# LPDDR4_SDRAM-1.net
KiCad netlist of a schematic drawn in Altium Designer
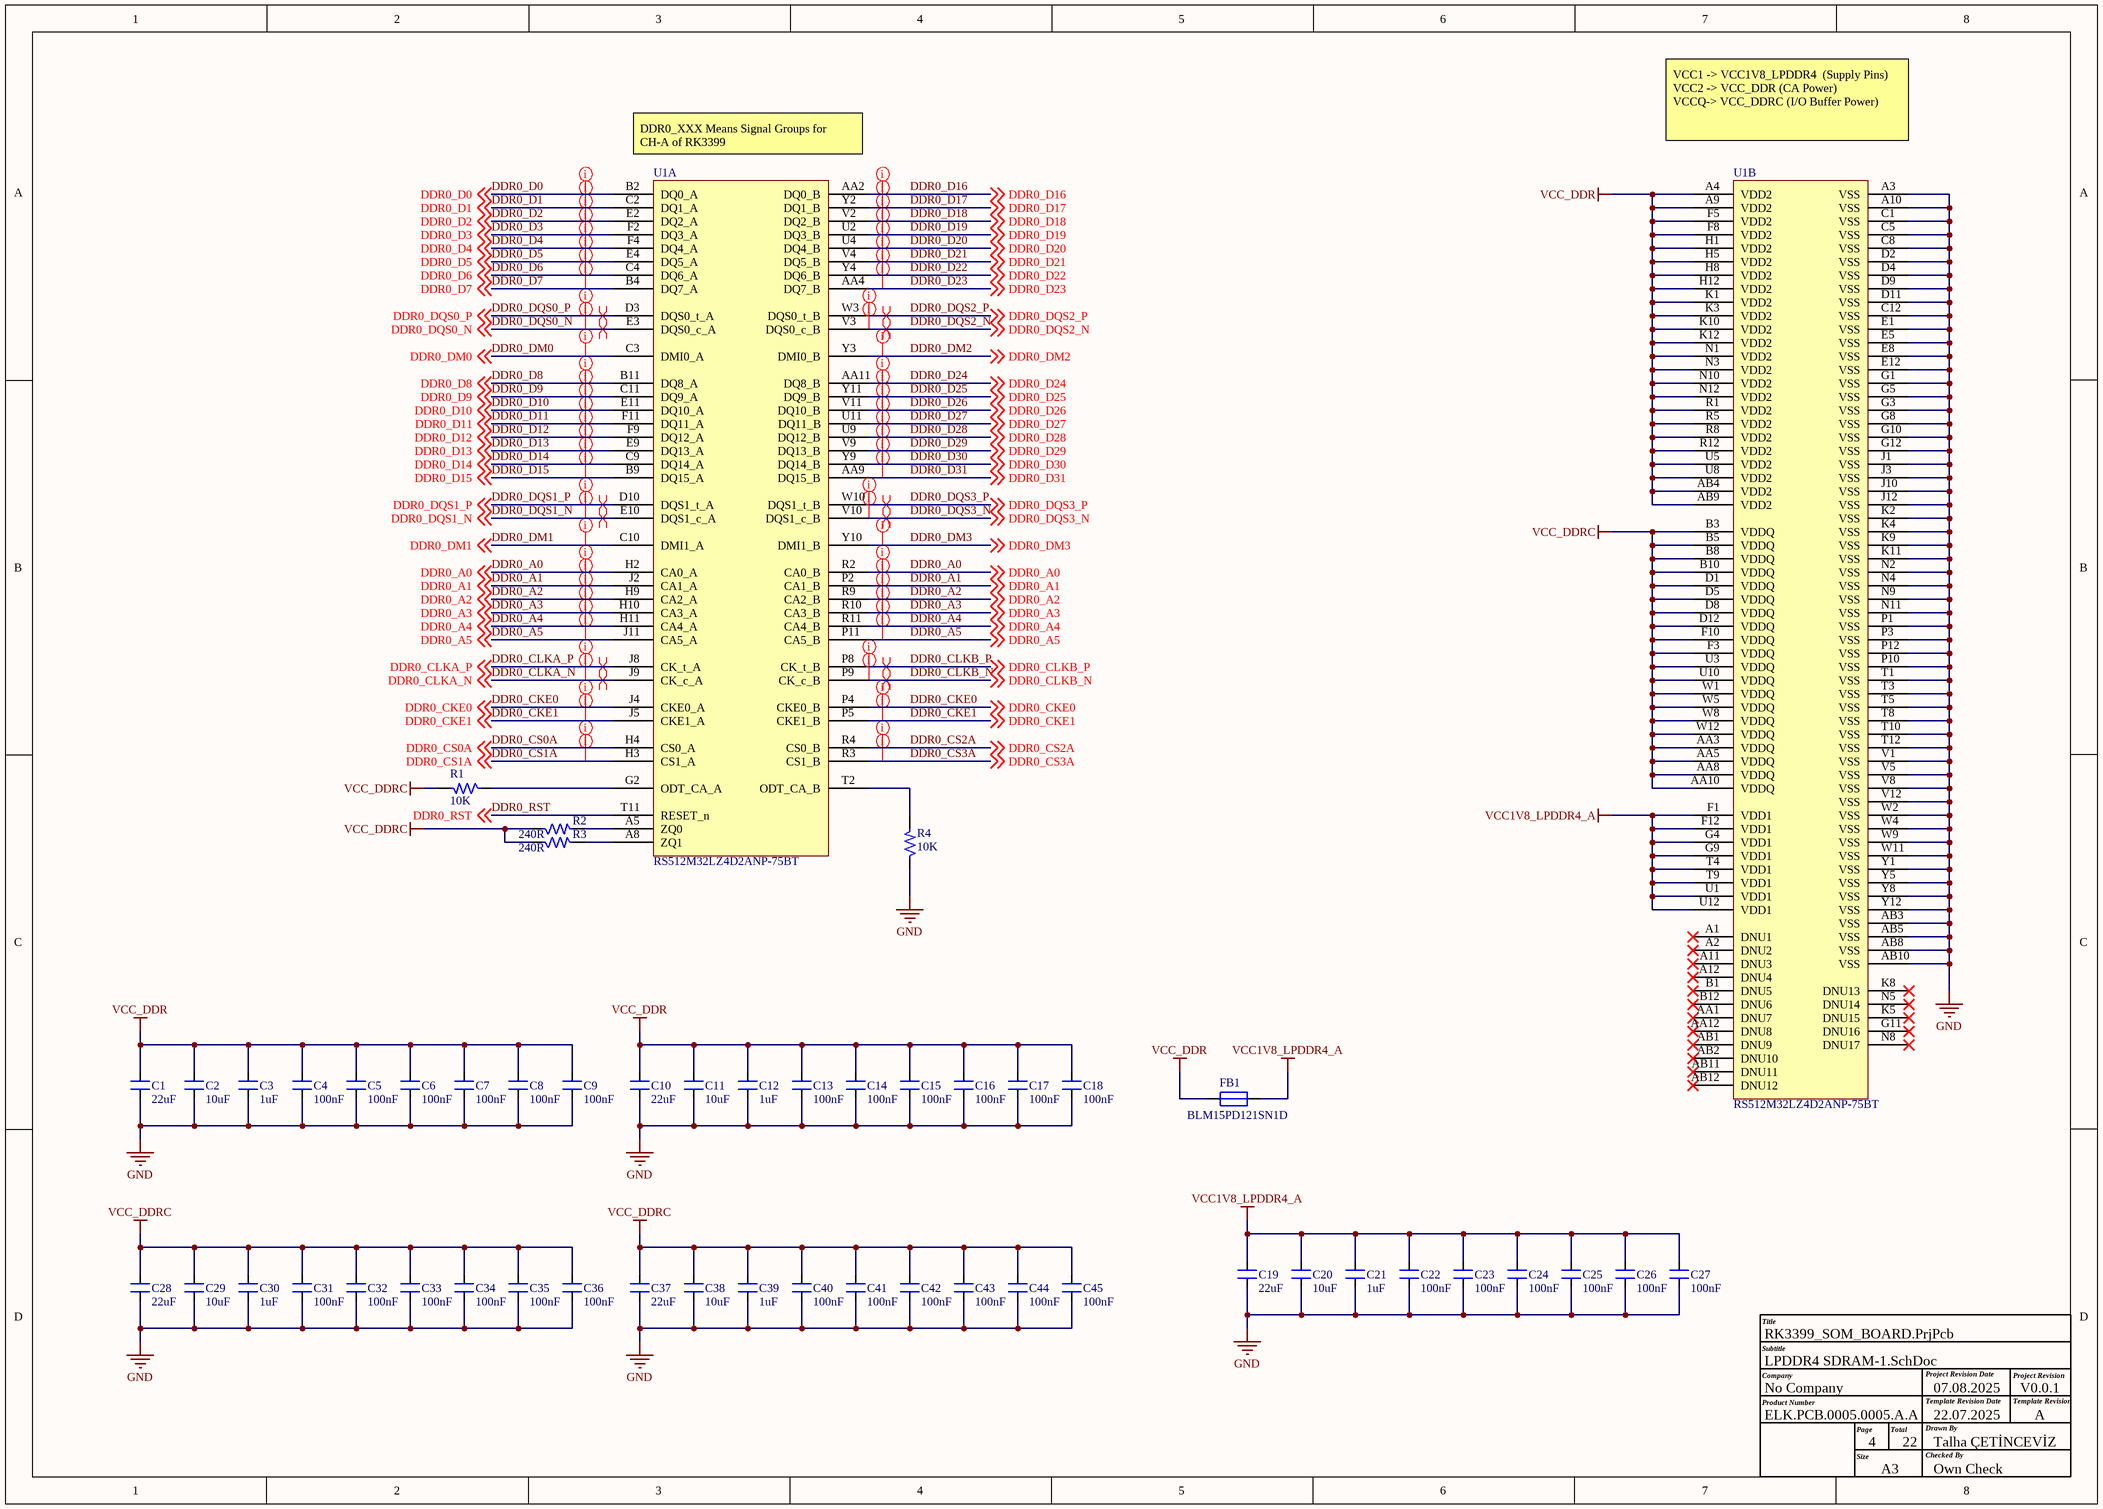
[diagram p0: LPDDR4 SDRAM-1.SchDoc]

(export (version "E")
  (design (tool "Eeschema 10.0.6"))
  (components
    (comp (ref "C1")
      (value "22uF")
      (footprint "CAP_0402")
      (description "22µF ±20% 6.3V Ceramic Capacitor X5R 0402 (1005 Metric)")
      (fields
        (field (name "MANUFACTURER") "Murata Electronics")
        (field (name "MANUFACTURER PART NUMBER") "CL05A226MQ5N6J8")
      )
      (libsource (lib "EsteemPCB_SOM_Course_intlib") (part "CAP_22uF-6.3V-20%-0402"))
    )
    (comp (ref "C2")
      (value "10uF")
      (footprint "CAP_0402")
      (description "10µF ±20% 10V Ceramic Capacitor X5R 0402 (1005 Metric)")
      (fields
        (field (name "MANUFACTURER PART NUMBER") "CL05A106MP5NUNC")
        (field (name "MANUFACTURER") "Samsung Electro-Mechanics")
      )
      (libsource (lib "EsteemPCB_SOM_Course_intlib") (part "CAP_10uF-10V-20%-0402"))
    )
    (comp (ref "C3")
      (value "1uF")
      (footprint "CAP_0201")
      (description "1µF ±20% 16V Ceramic Capacitor X5R 0201 (0603 Metric)")
      (fields
        (field (name "MANUFACTURER") "Samsung Electro-Mechanics")
        (field (name "MANUFACTURER PART NUMBER") "CL03A105MO3NRNH")
      )
      (libsource (lib "EsteemPCB_SOM_Course_intlib") (part "CAP_1uF-16V-10%-0201"))
    )
    (comp (ref "C4")
      (value "100nF")
      (footprint "CAP_0201")
      (description "0.1µF ±10% 25V Ceramic Capacitor X5R 0201 (0603 Metric)")
      (fields
        (field (name "MANUFACTURER") "TDK Corporation")
        (field (name "MANUFACTURER PART NUMBER") "C0603X5R1E104K030BB")
      )
      (libsource (lib "EsteemPCB_SOM_Course_intlib") (part "CAP_100nF-25V-10%-0201"))
    )
    (comp (ref "C5")
      (value "100nF")
      (footprint "CAP_0201")
      (description "0.1µF ±10% 25V Ceramic Capacitor X5R 0201 (0603 Metric)")
      (fields
        (field (name "MANUFACTURER") "TDK Corporation")
        (field (name "MANUFACTURER PART NUMBER") "C0603X5R1E104K030BB")
      )
      (libsource (lib "EsteemPCB_SOM_Course_intlib") (part "CAP_100nF-25V-10%-0201"))
    )
    (comp (ref "C6")
      (value "100nF")
      (footprint "CAP_0201")
      (description "0.1µF ±10% 25V Ceramic Capacitor X5R 0201 (0603 Metric)")
      (fields
        (field (name "MANUFACTURER") "TDK Corporation")
        (field (name "MANUFACTURER PART NUMBER") "C0603X5R1E104K030BB")
      )
      (libsource (lib "EsteemPCB_SOM_Course_intlib") (part "CAP_100nF-25V-10%-0201"))
    )
    (comp (ref "C7")
      (value "100nF")
      (footprint "CAP_0201")
      (description "0.1µF ±10% 25V Ceramic Capacitor X5R 0201 (0603 Metric)")
      (fields
        (field (name "MANUFACTURER") "TDK Corporation")
        (field (name "MANUFACTURER PART NUMBER") "C0603X5R1E104K030BB")
      )
      (libsource (lib "EsteemPCB_SOM_Course_intlib") (part "CAP_100nF-25V-10%-0201"))
    )
    (comp (ref "C8")
      (value "100nF")
      (footprint "CAP_0201")
      (description "0.1µF ±10% 25V Ceramic Capacitor X5R 0201 (0603 Metric)")
      (fields
        (field (name "MANUFACTURER") "TDK Corporation")
        (field (name "MANUFACTURER PART NUMBER") "C0603X5R1E104K030BB")
      )
      (libsource (lib "EsteemPCB_SOM_Course_intlib") (part "CAP_100nF-25V-10%-0201"))
    )
    (comp (ref "C9")
      (value "100nF")
      (footprint "CAP_0201")
      (description "0.1µF ±10% 25V Ceramic Capacitor X5R 0201 (0603 Metric)")
      (fields
        (field (name "MANUFACTURER") "TDK Corporation")
        (field (name "MANUFACTURER PART NUMBER") "C0603X5R1E104K030BB")
      )
      (libsource (lib "EsteemPCB_SOM_Course_intlib") (part "CAP_100nF-25V-10%-0201"))
    )
    (comp (ref "C10")
      (value "22uF")
      (footprint "CAP_0402")
      (description "22µF ±20% 6.3V Ceramic Capacitor X5R 0402 (1005 Metric)")
      (fields
        (field (name "MANUFACTURER") "Murata Electronics")
        (field (name "MANUFACTURER PART NUMBER") "CL05A226MQ5N6J8")
      )
      (libsource (lib "EsteemPCB_SOM_Course_intlib") (part "CAP_22uF-6.3V-20%-0402"))
    )
    (comp (ref "C11")
      (value "10uF")
      (footprint "CAP_0402")
      (description "10µF ±20% 10V Ceramic Capacitor X5R 0402 (1005 Metric)")
      (fields
        (field (name "MANUFACTURER PART NUMBER") "CL05A106MP5NUNC")
        (field (name "MANUFACTURER") "Samsung Electro-Mechanics")
      )
      (libsource (lib "EsteemPCB_SOM_Course_intlib") (part "CAP_10uF-10V-20%-0402"))
    )
    (comp (ref "C12")
      (value "1uF")
      (footprint "CAP_0201")
      (description "1µF ±20% 16V Ceramic Capacitor X5R 0201 (0603 Metric)")
      (fields
        (field (name "MANUFACTURER") "Samsung Electro-Mechanics")
        (field (name "MANUFACTURER PART NUMBER") "CL03A105MO3NRNH")
      )
      (libsource (lib "EsteemPCB_SOM_Course_intlib") (part "CAP_1uF-16V-10%-0201"))
    )
    (comp (ref "C13")
      (value "100nF")
      (footprint "CAP_0201")
      (description "0.1µF ±10% 25V Ceramic Capacitor X5R 0201 (0603 Metric)")
      (fields
        (field (name "MANUFACTURER") "TDK Corporation")
        (field (name "MANUFACTURER PART NUMBER") "C0603X5R1E104K030BB")
      )
      (libsource (lib "EsteemPCB_SOM_Course_intlib") (part "CAP_100nF-25V-10%-0201"))
    )
    (comp (ref "C14")
      (value "100nF")
      (footprint "CAP_0201")
      (description "0.1µF ±10% 25V Ceramic Capacitor X5R 0201 (0603 Metric)")
      (fields
        (field (name "MANUFACTURER") "TDK Corporation")
        (field (name "MANUFACTURER PART NUMBER") "C0603X5R1E104K030BB")
      )
      (libsource (lib "EsteemPCB_SOM_Course_intlib") (part "CAP_100nF-25V-10%-0201"))
    )
    (comp (ref "C15")
      (value "100nF")
      (footprint "CAP_0201")
      (description "0.1µF ±10% 25V Ceramic Capacitor X5R 0201 (0603 Metric)")
      (fields
        (field (name "MANUFACTURER") "TDK Corporation")
        (field (name "MANUFACTURER PART NUMBER") "C0603X5R1E104K030BB")
      )
      (libsource (lib "EsteemPCB_SOM_Course_intlib") (part "CAP_100nF-25V-10%-0201"))
    )
    (comp (ref "C16")
      (value "100nF")
      (footprint "CAP_0201")
      (description "0.1µF ±10% 25V Ceramic Capacitor X5R 0201 (0603 Metric)")
      (fields
        (field (name "MANUFACTURER") "TDK Corporation")
        (field (name "MANUFACTURER PART NUMBER") "C0603X5R1E104K030BB")
      )
      (libsource (lib "EsteemPCB_SOM_Course_intlib") (part "CAP_100nF-25V-10%-0201"))
    )
    (comp (ref "C17")
      (value "100nF")
      (footprint "CAP_0201")
      (description "0.1µF ±10% 25V Ceramic Capacitor X5R 0201 (0603 Metric)")
      (fields
        (field (name "MANUFACTURER") "TDK Corporation")
        (field (name "MANUFACTURER PART NUMBER") "C0603X5R1E104K030BB")
      )
      (libsource (lib "EsteemPCB_SOM_Course_intlib") (part "CAP_100nF-25V-10%-0201"))
    )
    (comp (ref "C18")
      (value "100nF")
      (footprint "CAP_0201")
      (description "0.1µF ±10% 25V Ceramic Capacitor X5R 0201 (0603 Metric)")
      (fields
        (field (name "MANUFACTURER") "TDK Corporation")
        (field (name "MANUFACTURER PART NUMBER") "C0603X5R1E104K030BB")
      )
      (libsource (lib "EsteemPCB_SOM_Course_intlib") (part "CAP_100nF-25V-10%-0201"))
    )
    (comp (ref "C19")
      (value "22uF")
      (footprint "CAP_0402")
      (description "22µF ±20% 6.3V Ceramic Capacitor X5R 0402 (1005 Metric)")
      (fields
        (field (name "MANUFACTURER") "Murata Electronics")
        (field (name "MANUFACTURER PART NUMBER") "CL05A226MQ5N6J8")
      )
      (libsource (lib "EsteemPCB_SOM_Course_intlib") (part "CAP_22uF-6.3V-20%-0402"))
    )
    (comp (ref "C20")
      (value "10uF")
      (footprint "CAP_0402")
      (description "10µF ±20% 10V Ceramic Capacitor X5R 0402 (1005 Metric)")
      (fields
        (field (name "MANUFACTURER PART NUMBER") "CL05A106MP5NUNC")
        (field (name "MANUFACTURER") "Samsung Electro-Mechanics")
      )
      (libsource (lib "EsteemPCB_SOM_Course_intlib") (part "CAP_10uF-10V-20%-0402"))
    )
    (comp (ref "C21")
      (value "1uF")
      (footprint "CAP_0201")
      (description "1µF ±20% 16V Ceramic Capacitor X5R 0201 (0603 Metric)")
      (fields
        (field (name "MANUFACTURER") "Samsung Electro-Mechanics")
        (field (name "MANUFACTURER PART NUMBER") "CL03A105MO3NRNH")
      )
      (libsource (lib "EsteemPCB_SOM_Course_intlib") (part "CAP_1uF-16V-10%-0201"))
    )
    (comp (ref "C22")
      (value "100nF")
      (footprint "CAP_0201")
      (description "0.1µF ±10% 25V Ceramic Capacitor X5R 0201 (0603 Metric)")
      (fields
        (field (name "MANUFACTURER") "TDK Corporation")
        (field (name "MANUFACTURER PART NUMBER") "C0603X5R1E104K030BB")
      )
      (libsource (lib "EsteemPCB_SOM_Course_intlib") (part "CAP_100nF-25V-10%-0201"))
    )
    (comp (ref "C23")
      (value "100nF")
      (footprint "CAP_0201")
      (description "0.1µF ±10% 25V Ceramic Capacitor X5R 0201 (0603 Metric)")
      (fields
        (field (name "MANUFACTURER") "TDK Corporation")
        (field (name "MANUFACTURER PART NUMBER") "C0603X5R1E104K030BB")
      )
      (libsource (lib "EsteemPCB_SOM_Course_intlib") (part "CAP_100nF-25V-10%-0201"))
    )
    (comp (ref "C24")
      (value "100nF")
      (footprint "CAP_0201")
      (description "0.1µF ±10% 25V Ceramic Capacitor X5R 0201 (0603 Metric)")
      (fields
        (field (name "MANUFACTURER") "TDK Corporation")
        (field (name "MANUFACTURER PART NUMBER") "C0603X5R1E104K030BB")
      )
      (libsource (lib "EsteemPCB_SOM_Course_intlib") (part "CAP_100nF-25V-10%-0201"))
    )
    (comp (ref "C25")
      (value "100nF")
      (footprint "CAP_0201")
      (description "0.1µF ±10% 25V Ceramic Capacitor X5R 0201 (0603 Metric)")
      (fields
        (field (name "MANUFACTURER") "TDK Corporation")
        (field (name "MANUFACTURER PART NUMBER") "C0603X5R1E104K030BB")
      )
      (libsource (lib "EsteemPCB_SOM_Course_intlib") (part "CAP_100nF-25V-10%-0201"))
    )
    (comp (ref "C26")
      (value "100nF")
      (footprint "CAP_0201")
      (description "0.1µF ±10% 25V Ceramic Capacitor X5R 0201 (0603 Metric)")
      (fields
        (field (name "MANUFACTURER") "TDK Corporation")
        (field (name "MANUFACTURER PART NUMBER") "C0603X5R1E104K030BB")
      )
      (libsource (lib "EsteemPCB_SOM_Course_intlib") (part "CAP_100nF-25V-10%-0201"))
    )
    (comp (ref "C27")
      (value "100nF")
      (footprint "CAP_0201")
      (description "0.1µF ±10% 25V Ceramic Capacitor X5R 0201 (0603 Metric)")
      (fields
        (field (name "MANUFACTURER") "TDK Corporation")
        (field (name "MANUFACTURER PART NUMBER") "C0603X5R1E104K030BB")
      )
      (libsource (lib "EsteemPCB_SOM_Course_intlib") (part "CAP_100nF-25V-10%-0201"))
    )
    (comp (ref "C28")
      (value "22uF")
      (footprint "CAP_0402")
      (description "22µF ±20% 6.3V Ceramic Capacitor X5R 0402 (1005 Metric)")
      (fields
        (field (name "MANUFACTURER") "Murata Electronics")
        (field (name "MANUFACTURER PART NUMBER") "CL05A226MQ5N6J8")
      )
      (libsource (lib "EsteemPCB_SOM_Course_intlib") (part "CAP_22uF-6.3V-20%-0402"))
    )
    (comp (ref "C29")
      (value "10uF")
      (footprint "CAP_0402")
      (description "10µF ±20% 10V Ceramic Capacitor X5R 0402 (1005 Metric)")
      (fields
        (field (name "MANUFACTURER PART NUMBER") "CL05A106MP5NUNC")
        (field (name "MANUFACTURER") "Samsung Electro-Mechanics")
      )
      (libsource (lib "EsteemPCB_SOM_Course_intlib") (part "CAP_10uF-10V-20%-0402"))
    )
    (comp (ref "C30")
      (value "1uF")
      (footprint "CAP_0201")
      (description "1µF ±20% 16V Ceramic Capacitor X5R 0201 (0603 Metric)")
      (fields
        (field (name "MANUFACTURER") "Samsung Electro-Mechanics")
        (field (name "MANUFACTURER PART NUMBER") "CL03A105MO3NRNH")
      )
      (libsource (lib "EsteemPCB_SOM_Course_intlib") (part "CAP_1uF-16V-10%-0201"))
    )
    (comp (ref "C31")
      (value "100nF")
      (footprint "CAP_0201")
      (description "0.1µF ±10% 25V Ceramic Capacitor X5R 0201 (0603 Metric)")
      (fields
        (field (name "MANUFACTURER") "TDK Corporation")
        (field (name "MANUFACTURER PART NUMBER") "C0603X5R1E104K030BB")
      )
      (libsource (lib "EsteemPCB_SOM_Course_intlib") (part "CAP_100nF-25V-10%-0201"))
    )
    (comp (ref "C32")
      (value "100nF")
      (footprint "CAP_0201")
      (description "0.1µF ±10% 25V Ceramic Capacitor X5R 0201 (0603 Metric)")
      (fields
        (field (name "MANUFACTURER") "TDK Corporation")
        (field (name "MANUFACTURER PART NUMBER") "C0603X5R1E104K030BB")
      )
      (libsource (lib "EsteemPCB_SOM_Course_intlib") (part "CAP_100nF-25V-10%-0201"))
    )
    (comp (ref "C33")
      (value "100nF")
      (footprint "CAP_0201")
      (description "0.1µF ±10% 25V Ceramic Capacitor X5R 0201 (0603 Metric)")
      (fields
        (field (name "MANUFACTURER") "TDK Corporation")
        (field (name "MANUFACTURER PART NUMBER") "C0603X5R1E104K030BB")
      )
      (libsource (lib "EsteemPCB_SOM_Course_intlib") (part "CAP_100nF-25V-10%-0201"))
    )
    (comp (ref "C34")
      (value "100nF")
      (footprint "CAP_0201")
      (description "0.1µF ±10% 25V Ceramic Capacitor X5R 0201 (0603 Metric)")
      (fields
        (field (name "MANUFACTURER") "TDK Corporation")
        (field (name "MANUFACTURER PART NUMBER") "C0603X5R1E104K030BB")
      )
      (libsource (lib "EsteemPCB_SOM_Course_intlib") (part "CAP_100nF-25V-10%-0201"))
    )
    (comp (ref "C35")
      (value "100nF")
      (footprint "CAP_0201")
      (description "0.1µF ±10% 25V Ceramic Capacitor X5R 0201 (0603 Metric)")
      (fields
        (field (name "MANUFACTURER") "TDK Corporation")
        (field (name "MANUFACTURER PART NUMBER") "C0603X5R1E104K030BB")
      )
      (libsource (lib "EsteemPCB_SOM_Course_intlib") (part "CAP_100nF-25V-10%-0201"))
    )
    (comp (ref "C36")
      (value "100nF")
      (footprint "CAP_0201")
      (description "0.1µF ±10% 25V Ceramic Capacitor X5R 0201 (0603 Metric)")
      (fields
        (field (name "MANUFACTURER") "TDK Corporation")
        (field (name "MANUFACTURER PART NUMBER") "C0603X5R1E104K030BB")
      )
      (libsource (lib "EsteemPCB_SOM_Course_intlib") (part "CAP_100nF-25V-10%-0201"))
    )
    (comp (ref "C37")
      (value "22uF")
      (footprint "CAP_0402")
      (description "22µF ±20% 6.3V Ceramic Capacitor X5R 0402 (1005 Metric)")
      (fields
        (field (name "MANUFACTURER") "Murata Electronics")
        (field (name "MANUFACTURER PART NUMBER") "CL05A226MQ5N6J8")
      )
      (libsource (lib "EsteemPCB_SOM_Course_intlib") (part "CAP_22uF-6.3V-20%-0402"))
    )
    (comp (ref "C38")
      (value "10uF")
      (footprint "CAP_0402")
      (description "10µF ±20% 10V Ceramic Capacitor X5R 0402 (1005 Metric)")
      (fields
        (field (name "MANUFACTURER PART NUMBER") "CL05A106MP5NUNC")
        (field (name "MANUFACTURER") "Samsung Electro-Mechanics")
      )
      (libsource (lib "EsteemPCB_SOM_Course_intlib") (part "CAP_10uF-10V-20%-0402"))
    )
    (comp (ref "C39")
      (value "1uF")
      (footprint "CAP_0201")
      (description "1µF ±20% 16V Ceramic Capacitor X5R 0201 (0603 Metric)")
      (fields
        (field (name "MANUFACTURER") "Samsung Electro-Mechanics")
        (field (name "MANUFACTURER PART NUMBER") "CL03A105MO3NRNH")
      )
      (libsource (lib "EsteemPCB_SOM_Course_intlib") (part "CAP_1uF-16V-10%-0201"))
    )
    (comp (ref "C40")
      (value "100nF")
      (footprint "CAP_0201")
      (description "0.1µF ±10% 25V Ceramic Capacitor X5R 0201 (0603 Metric)")
      (fields
        (field (name "MANUFACTURER") "TDK Corporation")
        (field (name "MANUFACTURER PART NUMBER") "C0603X5R1E104K030BB")
      )
      (libsource (lib "EsteemPCB_SOM_Course_intlib") (part "CAP_100nF-25V-10%-0201"))
    )
    (comp (ref "C41")
      (value "100nF")
      (footprint "CAP_0201")
      (description "0.1µF ±10% 25V Ceramic Capacitor X5R 0201 (0603 Metric)")
      (fields
        (field (name "MANUFACTURER") "TDK Corporation")
        (field (name "MANUFACTURER PART NUMBER") "C0603X5R1E104K030BB")
      )
      (libsource (lib "EsteemPCB_SOM_Course_intlib") (part "CAP_100nF-25V-10%-0201"))
    )
    (comp (ref "C42")
      (value "100nF")
      (footprint "CAP_0201")
      (description "0.1µF ±10% 25V Ceramic Capacitor X5R 0201 (0603 Metric)")
      (fields
        (field (name "MANUFACTURER") "TDK Corporation")
        (field (name "MANUFACTURER PART NUMBER") "C0603X5R1E104K030BB")
      )
      (libsource (lib "EsteemPCB_SOM_Course_intlib") (part "CAP_100nF-25V-10%-0201"))
    )
    (comp (ref "C43")
      (value "100nF")
      (footprint "CAP_0201")
      (description "0.1µF ±10% 25V Ceramic Capacitor X5R 0201 (0603 Metric)")
      (fields
        (field (name "MANUFACTURER") "TDK Corporation")
        (field (name "MANUFACTURER PART NUMBER") "C0603X5R1E104K030BB")
      )
      (libsource (lib "EsteemPCB_SOM_Course_intlib") (part "CAP_100nF-25V-10%-0201"))
    )
    (comp (ref "C44")
      (value "100nF")
      (footprint "CAP_0201")
      (description "0.1µF ±10% 25V Ceramic Capacitor X5R 0201 (0603 Metric)")
      (fields
        (field (name "MANUFACTURER") "TDK Corporation")
        (field (name "MANUFACTURER PART NUMBER") "C0603X5R1E104K030BB")
      )
      (libsource (lib "EsteemPCB_SOM_Course_intlib") (part "CAP_100nF-25V-10%-0201"))
    )
    (comp (ref "C45")
      (value "100nF")
      (footprint "CAP_0201")
      (description "0.1µF ±10% 25V Ceramic Capacitor X5R 0201 (0603 Metric)")
      (fields
        (field (name "MANUFACTURER") "TDK Corporation")
        (field (name "MANUFACTURER PART NUMBER") "C0603X5R1E104K030BB")
      )
      (libsource (lib "EsteemPCB_SOM_Course_intlib") (part "CAP_100nF-25V-10%-0201"))
    )
    (comp (ref "FB1")
      (value "BLM15PD121SN1D")
      (footprint "RES_0402")
      (description "120 Ohms @ 100MHz 1 Power Line Ferrite Bead 0402 (1005 Metric) 1.3A 90mOhm")
      (fields (field (name "MANUFACTURER") "Murata Electronics"))
      (libsource (lib "EsteemPCB_SOM_Course_intlib") (part "FB_120R-1.3A-100Mhz-0402"))
    )
    (comp (ref "R1")
      (value "10K")
      (footprint "RES_0201")
      (description "10 kOhms ±1% 0.05W, 1/20W Chip Resistor 0201 (0603 Metric) Thick Film")
      (fields
        (field (name "MANUFACTURER") "Stackpole Electronics Inc")
        (field (name "MANUFACTURER PART NUMBER") "RMCF0201FT10K0")
      )
      (libsource (lib "EsteemPCB_SOM_Course_intlib") (part "RES_10K-0.05W-1%-0201"))
    )
    (comp (ref "R2")
      (value "240R")
      (footprint "RES_0201")
      (description "240 Ohms ±1% 0.05W, 1/20W Chip Resistor 0201 (0603 Metric) Thick Film")
      (fields
        (field (name "MANUFACTURER") "Yageo")
        (field (name "MANUFACTURER PART NUMBER") "RC0201FR-07240RL")
      )
      (libsource (lib "EsteemPCB_SOM_Course_intlib") (part "RES_240R-0.05W-1%-0201"))
    )
    (comp (ref "R3")
      (value "240R")
      (footprint "RES_0201")
      (description "240 Ohms ±1% 0.05W, 1/20W Chip Resistor 0201 (0603 Metric) Thick Film")
      (fields
        (field (name "MANUFACTURER") "Yageo")
        (field (name "MANUFACTURER PART NUMBER") "RC0201FR-07240RL")
      )
      (libsource (lib "EsteemPCB_SOM_Course_intlib") (part "RES_240R-0.05W-1%-0201"))
    )
    (comp (ref "R4")
      (value "10K")
      (footprint "RES_0201")
      (description "10 kOhms ±1% 0.05W, 1/20W Chip Resistor 0201 (0603 Metric) Thick Film")
      (fields
        (field (name "MANUFACTURER") "Stackpole Electronics Inc")
        (field (name "MANUFACTURER PART NUMBER") "RMCF0201FT10K0")
      )
      (libsource (lib "EsteemPCB_SOM_Course_intlib") (part "RES_10K-0.05W-1%-0201"))
    )
    (comp (ref "U1")
      (value "RS512M32LZ4D2ANP-75BT")
      (footprint "FBGA200_SMD")
      (fields (field (name "MANUFACTURER") "RAYSON"))
      (libsource (lib "EsteemPCB_SOM_Course_intlib") (part "IC_RS512M32LZ4D2ANP-75BT"))
    )
  )
  (nets
    (net (code "1") (name "DDR0_A0") (class "Default")
      (node (ref "U1") (pin "H2") (pinfunction "CA0_A_H2") (pintype "passive"))
      (node (ref "U1") (pin "R2") (pinfunction "CA0_B_R2") (pintype "passive"))
    )
    (net (code "2") (name "DDR0_A1") (class "Default")
      (node (ref "U1") (pin "J2") (pinfunction "CA1_A_J2") (pintype "passive"))
      (node (ref "U1") (pin "P2") (pinfunction "CA1_B_P2") (pintype "passive"))
    )
    (net (code "3") (name "DDR0_A2") (class "Default")
      (node (ref "U1") (pin "H9") (pinfunction "CA2_A_H9") (pintype "passive"))
      (node (ref "U1") (pin "R9") (pinfunction "CA2_B_R9") (pintype "passive"))
    )
    (net (code "4") (name "DDR0_A3") (class "Default")
      (node (ref "U1") (pin "H10") (pinfunction "CA3_A_H10") (pintype "passive"))
      (node (ref "U1") (pin "R10") (pinfunction "CA3_B_R10") (pintype "passive"))
    )
    (net (code "5") (name "DDR0_A4") (class "Default")
      (node (ref "U1") (pin "H11") (pinfunction "CA4_A_H11") (pintype "passive"))
      (node (ref "U1") (pin "R11") (pinfunction "CA4_B_R11") (pintype "passive"))
    )
    (net (code "6") (name "DDR0_A5") (class "Default")
      (node (ref "U1") (pin "J11") (pinfunction "CA5_A_J11") (pintype "passive"))
      (node (ref "U1") (pin "P11") (pinfunction "CA5_B_P11") (pintype "passive"))
    )
    (net (code "7") (name "DDR0_CKE0") (class "Default")
      (node (ref "U1") (pin "J4") (pinfunction "CKE0_A_J4") (pintype "passive"))
      (node (ref "U1") (pin "P4") (pinfunction "CKE0_B_P4") (pintype "passive"))
    )
    (net (code "8") (name "DDR0_CKE1") (class "Default")
      (node (ref "U1") (pin "J5") (pinfunction "CKE1_A_J5") (pintype "passive"))
      (node (ref "U1") (pin "P5") (pinfunction "CKE1_B_P5") (pintype "passive"))
    )
    (net (code "9") (name "DDR0_CLKA_N") (class "Default")
      (node (ref "U1") (pin "J9") (pinfunction "CK_c_A_J9") (pintype "passive"))
    )
    (net (code "10") (name "DDR0_CLKA_P") (class "Default")
      (node (ref "U1") (pin "J8") (pinfunction "CK_t_A_J8") (pintype "passive"))
    )
    (net (code "11") (name "DDR0_CLKB_N") (class "Default")
      (node (ref "U1") (pin "P9") (pinfunction "CK_c_B_P9") (pintype "passive"))
    )
    (net (code "12") (name "DDR0_CLKB_P") (class "Default")
      (node (ref "U1") (pin "P8") (pinfunction "CK_t_B_P8") (pintype "passive"))
    )
    (net (code "13") (name "DDR0_CS0A") (class "Default")
      (node (ref "U1") (pin "H4") (pinfunction "CS0_A_H4") (pintype "passive"))
    )
    (net (code "14") (name "DDR0_CS1A") (class "Default")
      (node (ref "U1") (pin "H3") (pinfunction "CS1_A_H3") (pintype "passive"))
    )
    (net (code "15") (name "DDR0_CS2A") (class "Default")
      (node (ref "U1") (pin "R4") (pinfunction "CS0_B_R4") (pintype "passive"))
    )
    (net (code "16") (name "DDR0_CS3A") (class "Default")
      (node (ref "U1") (pin "R3") (pinfunction "CS1_B_R3") (pintype "passive"))
    )
    (net (code "17") (name "DDR0_D0") (class "Default")
      (node (ref "U1") (pin "B2") (pinfunction "DQ0_A_B2") (pintype "passive"))
    )
    (net (code "18") (name "DDR0_D1") (class "Default")
      (node (ref "U1") (pin "C2") (pinfunction "DQ1_A_C2") (pintype "passive"))
    )
    (net (code "19") (name "DDR0_D2") (class "Default")
      (node (ref "U1") (pin "E2") (pinfunction "DQ2_A_E2") (pintype "passive"))
    )
    (net (code "20") (name "DDR0_D3") (class "Default")
      (node (ref "U1") (pin "F2") (pinfunction "DQ3_A_F2") (pintype "passive"))
    )
    (net (code "21") (name "DDR0_D4") (class "Default")
      (node (ref "U1") (pin "F4") (pinfunction "DQ4_A_F4") (pintype "passive"))
    )
    (net (code "22") (name "DDR0_D5") (class "Default")
      (node (ref "U1") (pin "E4") (pinfunction "DQ5_A_E4") (pintype "passive"))
    )
    (net (code "23") (name "DDR0_D6") (class "Default")
      (node (ref "U1") (pin "C4") (pinfunction "DQ6_A_C4") (pintype "passive"))
    )
    (net (code "24") (name "DDR0_D7") (class "Default")
      (node (ref "U1") (pin "B4") (pinfunction "DQ7_A_B4") (pintype "passive"))
    )
    (net (code "25") (name "DDR0_D8") (class "Default")
      (node (ref "U1") (pin "B11") (pinfunction "DQ8_A_B11") (pintype "passive"))
    )
    (net (code "26") (name "DDR0_D9") (class "Default")
      (node (ref "U1") (pin "C11") (pinfunction "DQ9_A_C11") (pintype "passive"))
    )
    (net (code "27") (name "DDR0_D10") (class "Default")
      (node (ref "U1") (pin "E11") (pinfunction "DQ10_A_E11") (pintype "passive"))
    )
    (net (code "28") (name "DDR0_D11") (class "Default")
      (node (ref "U1") (pin "F11") (pinfunction "DQ11_A_F11") (pintype "passive"))
    )
    (net (code "29") (name "DDR0_D12") (class "Default")
      (node (ref "U1") (pin "F9") (pinfunction "DQ12_A_F9") (pintype "passive"))
    )
    (net (code "30") (name "DDR0_D13") (class "Default")
      (node (ref "U1") (pin "E9") (pinfunction "DQ13_A_E9") (pintype "passive"))
    )
    (net (code "31") (name "DDR0_D14") (class "Default")
      (node (ref "U1") (pin "C9") (pinfunction "DQ14_A_C9") (pintype "passive"))
    )
    (net (code "32") (name "DDR0_D15") (class "Default")
      (node (ref "U1") (pin "B9") (pinfunction "DQ15_A_B9") (pintype "passive"))
    )
    (net (code "33") (name "DDR0_D16") (class "Default")
      (node (ref "U1") (pin "AA2") (pinfunction "DQ0_B_AA2") (pintype "passive"))
    )
    (net (code "34") (name "DDR0_D17") (class "Default")
      (node (ref "U1") (pin "Y2") (pinfunction "DQ1_B_Y2") (pintype "passive"))
    )
    (net (code "35") (name "DDR0_D18") (class "Default")
      (node (ref "U1") (pin "V2") (pinfunction "DQ2_B_V2") (pintype "passive"))
    )
    (net (code "36") (name "DDR0_D19") (class "Default")
      (node (ref "U1") (pin "U2") (pinfunction "DQ3_B_U2") (pintype "passive"))
    )
    (net (code "37") (name "DDR0_D20") (class "Default")
      (node (ref "U1") (pin "U4") (pinfunction "DQ4_B_U4") (pintype "passive"))
    )
    (net (code "38") (name "DDR0_D21") (class "Default")
      (node (ref "U1") (pin "V4") (pinfunction "DQ5_B_V4") (pintype "passive"))
    )
    (net (code "39") (name "DDR0_D22") (class "Default")
      (node (ref "U1") (pin "Y4") (pinfunction "DQ6_B_Y4") (pintype "passive"))
    )
    (net (code "40") (name "DDR0_D23") (class "Default")
      (node (ref "U1") (pin "AA4") (pinfunction "DQ7_B_AA4") (pintype "passive"))
    )
    (net (code "41") (name "DDR0_D24") (class "Default")
      (node (ref "U1") (pin "AA11") (pinfunction "DQ8_B_AA11") (pintype "passive"))
    )
    (net (code "42") (name "DDR0_D25") (class "Default")
      (node (ref "U1") (pin "Y11") (pinfunction "DQ9_B_Y11") (pintype "passive"))
    )
    (net (code "43") (name "DDR0_D26") (class "Default")
      (node (ref "U1") (pin "V11") (pinfunction "DQ10_B_V11") (pintype "passive"))
    )
    (net (code "44") (name "DDR0_D27") (class "Default")
      (node (ref "U1") (pin "U11") (pinfunction "DQ11_B_U11") (pintype "passive"))
    )
    (net (code "45") (name "DDR0_D28") (class "Default")
      (node (ref "U1") (pin "U9") (pinfunction "DQ12_B_U9") (pintype "passive"))
    )
    (net (code "46") (name "DDR0_D29") (class "Default")
      (node (ref "U1") (pin "V9") (pinfunction "DQ13_B_V9") (pintype "passive"))
    )
    (net (code "47") (name "DDR0_D30") (class "Default")
      (node (ref "U1") (pin "Y9") (pinfunction "DQ14_B_Y9") (pintype "passive"))
    )
    (net (code "48") (name "DDR0_D31") (class "Default")
      (node (ref "U1") (pin "AA9") (pinfunction "DQ15_B_AA9") (pintype "passive"))
    )
    (net (code "49") (name "DDR0_DM0") (class "Default")
      (node (ref "U1") (pin "C3") (pinfunction "DMI0_A_C3") (pintype "passive"))
    )
    (net (code "50") (name "DDR0_DM1") (class "Default")
      (node (ref "U1") (pin "C10") (pinfunction "DMI1_A_C10") (pintype "passive"))
    )
    (net (code "51") (name "DDR0_DM2") (class "Default")
      (node (ref "U1") (pin "Y3") (pinfunction "DMI0_B_Y3") (pintype "passive"))
    )
    (net (code "52") (name "DDR0_DM3") (class "Default")
      (node (ref "U1") (pin "Y10") (pinfunction "DMI1_B_Y10") (pintype "passive"))
    )
    (net (code "53") (name "DDR0_DQS0_N") (class "Default")
      (node (ref "U1") (pin "E3") (pinfunction "DQS0_c_A_E3") (pintype "passive"))
    )
    (net (code "54") (name "DDR0_DQS0_P") (class "Default")
      (node (ref "U1") (pin "D3") (pinfunction "DQS0_t_A_D3") (pintype "passive"))
    )
    (net (code "55") (name "DDR0_DQS1_N") (class "Default")
      (node (ref "U1") (pin "E10") (pinfunction "DQS1_c_A_E10") (pintype "passive"))
    )
    (net (code "56") (name "DDR0_DQS1_P") (class "Default")
      (node (ref "U1") (pin "D10") (pinfunction "DQS1_t_A_D10") (pintype "passive"))
    )
    (net (code "57") (name "DDR0_DQS2_N") (class "Default")
      (node (ref "U1") (pin "V3") (pinfunction "DQS0_c_B_V3") (pintype "passive"))
    )
    (net (code "58") (name "DDR0_DQS2_P") (class "Default")
      (node (ref "U1") (pin "W3") (pinfunction "DQS0_t_B_W3") (pintype "passive"))
    )
    (net (code "59") (name "DDR0_DQS3_N") (class "Default")
      (node (ref "U1") (pin "V10") (pinfunction "DQS1_c_B_V10") (pintype "passive"))
    )
    (net (code "60") (name "DDR0_DQS3_P") (class "Default")
      (node (ref "U1") (pin "W10") (pinfunction "DQS1_t_B_W10") (pintype "passive"))
    )
    (net (code "61") (name "DDR0_RST") (class "Default")
      (node (ref "U1") (pin "T11") (pinfunction "RESET_n_T11") (pintype "passive"))
    )
    (net (code "62") (name "GND") (class "Default")
      (node (ref "C1") (pin "1") (pinfunction "1_1") (pintype "passive"))
      (node (ref "C10") (pin "1") (pinfunction "1_1") (pintype "passive"))
      (node (ref "C11") (pin "1") (pinfunction "1_1") (pintype "passive"))
      (node (ref "C12") (pin "1") (pinfunction "1_1") (pintype "passive"))
      (node (ref "C13") (pin "1") (pinfunction "1_1") (pintype "passive"))
      (node (ref "C14") (pin "1") (pinfunction "1_1") (pintype "passive"))
      (node (ref "C15") (pin "1") (pinfunction "1_1") (pintype "passive"))
      (node (ref "C16") (pin "1") (pinfunction "1_1") (pintype "passive"))
      (node (ref "C17") (pin "1") (pinfunction "1_1") (pintype "passive"))
      (node (ref "C18") (pin "1") (pinfunction "1_1") (pintype "passive"))
      (node (ref "C19") (pin "1") (pinfunction "1_1") (pintype "passive"))
      (node (ref "C2") (pin "1") (pinfunction "1_1") (pintype "passive"))
      (node (ref "C20") (pin "1") (pinfunction "1_1") (pintype "passive"))
      (node (ref "C21") (pin "1") (pinfunction "1_1") (pintype "passive"))
      (node (ref "C22") (pin "1") (pinfunction "1_1") (pintype "passive"))
      (node (ref "C23") (pin "1") (pinfunction "1_1") (pintype "passive"))
      (node (ref "C24") (pin "1") (pinfunction "1_1") (pintype "passive"))
      (node (ref "C25") (pin "1") (pinfunction "1_1") (pintype "passive"))
      (node (ref "C26") (pin "1") (pinfunction "1_1") (pintype "passive"))
      (node (ref "C27") (pin "1") (pinfunction "1_1") (pintype "passive"))
      (node (ref "C28") (pin "1") (pinfunction "1_1") (pintype "passive"))
      (node (ref "C29") (pin "1") (pinfunction "1_1") (pintype "passive"))
      (node (ref "C3") (pin "1") (pinfunction "1_1") (pintype "passive"))
      (node (ref "C30") (pin "1") (pinfunction "1_1") (pintype "passive"))
      (node (ref "C31") (pin "1") (pinfunction "1_1") (pintype "passive"))
      (node (ref "C32") (pin "1") (pinfunction "1_1") (pintype "passive"))
      (node (ref "C33") (pin "1") (pinfunction "1_1") (pintype "passive"))
      (node (ref "C34") (pin "1") (pinfunction "1_1") (pintype "passive"))
      (node (ref "C35") (pin "1") (pinfunction "1_1") (pintype "passive"))
      (node (ref "C36") (pin "1") (pinfunction "1_1") (pintype "passive"))
      (node (ref "C37") (pin "1") (pinfunction "1_1") (pintype "passive"))
      (node (ref "C38") (pin "1") (pinfunction "1_1") (pintype "passive"))
      (node (ref "C39") (pin "1") (pinfunction "1_1") (pintype "passive"))
      (node (ref "C4") (pin "1") (pinfunction "1_1") (pintype "passive"))
      (node (ref "C40") (pin "1") (pinfunction "1_1") (pintype "passive"))
      (node (ref "C41") (pin "1") (pinfunction "1_1") (pintype "passive"))
      (node (ref "C42") (pin "1") (pinfunction "1_1") (pintype "passive"))
      (node (ref "C43") (pin "1") (pinfunction "1_1") (pintype "passive"))
      (node (ref "C44") (pin "1") (pinfunction "1_1") (pintype "passive"))
      (node (ref "C45") (pin "1") (pinfunction "1_1") (pintype "passive"))
      (node (ref "C5") (pin "1") (pinfunction "1_1") (pintype "passive"))
      (node (ref "C6") (pin "1") (pinfunction "1_1") (pintype "passive"))
      (node (ref "C7") (pin "1") (pinfunction "1_1") (pintype "passive"))
      (node (ref "C8") (pin "1") (pinfunction "1_1") (pintype "passive"))
      (node (ref "C9") (pin "1") (pinfunction "1_1") (pintype "passive"))
      (node (ref "R4") (pin "1") (pinfunction "1_1") (pintype "passive"))
      (node (ref "U1") (pin "A10") (pinfunction "VSS_A10") (pintype "passive"))
      (node (ref "U1") (pin "A3") (pinfunction "VSS_A3") (pintype "passive"))
      (node (ref "U1") (pin "AB10") (pinfunction "VSS_AB10") (pintype "passive"))
      (node (ref "U1") (pin "AB3") (pinfunction "VSS_AB3") (pintype "passive"))
      (node (ref "U1") (pin "AB5") (pinfunction "VSS_AB5") (pintype "passive"))
      (node (ref "U1") (pin "AB8") (pinfunction "VSS_AB8") (pintype "passive"))
      (node (ref "U1") (pin "C1") (pinfunction "VSS_C1") (pintype "passive"))
      (node (ref "U1") (pin "C12") (pinfunction "VSS_C12") (pintype "passive"))
      (node (ref "U1") (pin "C5") (pinfunction "VSS_C5") (pintype "passive"))
      (node (ref "U1") (pin "C8") (pinfunction "VSS_C8") (pintype "passive"))
      (node (ref "U1") (pin "D11") (pinfunction "VSS_D11") (pintype "passive"))
      (node (ref "U1") (pin "D2") (pinfunction "VSS_D2") (pintype "passive"))
      (node (ref "U1") (pin "D4") (pinfunction "VSS_D4") (pintype "passive"))
      (node (ref "U1") (pin "D9") (pinfunction "VSS_D9") (pintype "passive"))
      (node (ref "U1") (pin "E1") (pinfunction "VSS_E1") (pintype "passive"))
      (node (ref "U1") (pin "E12") (pinfunction "VSS_E12") (pintype "passive"))
      (node (ref "U1") (pin "E5") (pinfunction "VSS_E5") (pintype "passive"))
      (node (ref "U1") (pin "E8") (pinfunction "VSS_E8") (pintype "passive"))
      (node (ref "U1") (pin "G1") (pinfunction "VSS_G1") (pintype "passive"))
      (node (ref "U1") (pin "G10") (pinfunction "VSS_G10") (pintype "passive"))
      (node (ref "U1") (pin "G12") (pinfunction "VSS_G12") (pintype "passive"))
      (node (ref "U1") (pin "G3") (pinfunction "VSS_G3") (pintype "passive"))
      (node (ref "U1") (pin "G5") (pinfunction "VSS_G5") (pintype "passive"))
      (node (ref "U1") (pin "G8") (pinfunction "VSS_G8") (pintype "passive"))
      (node (ref "U1") (pin "J1") (pinfunction "VSS_J1") (pintype "passive"))
      (node (ref "U1") (pin "J10") (pinfunction "VSS_J10") (pintype "passive"))
      (node (ref "U1") (pin "J12") (pinfunction "VSS_J12") (pintype "passive"))
      (node (ref "U1") (pin "J3") (pinfunction "VSS_J3") (pintype "passive"))
      (node (ref "U1") (pin "K11") (pinfunction "VSS_K11") (pintype "passive"))
      (node (ref "U1") (pin "K2") (pinfunction "VSS_K2") (pintype "passive"))
      (node (ref "U1") (pin "K4") (pinfunction "VSS_K4") (pintype "passive"))
      (node (ref "U1") (pin "K9") (pinfunction "VSS_K9") (pintype "passive"))
      (node (ref "U1") (pin "N11") (pinfunction "VSS_N11") (pintype "passive"))
      (node (ref "U1") (pin "N2") (pinfunction "VSS_N2") (pintype "passive"))
      (node (ref "U1") (pin "N4") (pinfunction "VSS_N4") (pintype "passive"))
      (node (ref "U1") (pin "N9") (pinfunction "VSS_N9") (pintype "passive"))
      (node (ref "U1") (pin "P1") (pinfunction "VSS_P1") (pintype "passive"))
      (node (ref "U1") (pin "P10") (pinfunction "VSS_P10") (pintype "passive"))
      (node (ref "U1") (pin "P12") (pinfunction "VSS_P12") (pintype "passive"))
      (node (ref "U1") (pin "P3") (pinfunction "VSS_P3") (pintype "passive"))
      (node (ref "U1") (pin "T1") (pinfunction "VSS_T1") (pintype "passive"))
      (node (ref "U1") (pin "T10") (pinfunction "VSS_T10") (pintype "passive"))
      (node (ref "U1") (pin "T12") (pinfunction "VSS_T12") (pintype "passive"))
      (node (ref "U1") (pin "T3") (pinfunction "VSS_T3") (pintype "passive"))
      (node (ref "U1") (pin "T5") (pinfunction "VSS_T5") (pintype "passive"))
      (node (ref "U1") (pin "T8") (pinfunction "VSS_T8") (pintype "passive"))
      (node (ref "U1") (pin "V1") (pinfunction "VSS_V1") (pintype "passive"))
      (node (ref "U1") (pin "V12") (pinfunction "VSS_V12") (pintype "passive"))
      (node (ref "U1") (pin "V5") (pinfunction "VSS_V5") (pintype "passive"))
      (node (ref "U1") (pin "V8") (pinfunction "VSS_V8") (pintype "passive"))
      (node (ref "U1") (pin "W11") (pinfunction "VSS_W11") (pintype "passive"))
      (node (ref "U1") (pin "W2") (pinfunction "VSS_W2") (pintype "passive"))
      (node (ref "U1") (pin "W4") (pinfunction "VSS_W4") (pintype "passive"))
      (node (ref "U1") (pin "W9") (pinfunction "VSS_W9") (pintype "passive"))
      (node (ref "U1") (pin "Y1") (pinfunction "VSS_Y1") (pintype "passive"))
      (node (ref "U1") (pin "Y12") (pinfunction "VSS_Y12") (pintype "passive"))
      (node (ref "U1") (pin "Y5") (pinfunction "VSS_Y5") (pintype "passive"))
      (node (ref "U1") (pin "Y8") (pinfunction "VSS_Y8") (pintype "passive"))
    )
    (net (code "63") (name "Net-(U1A-ODT_CA_A)") (class "Default")
      (node (ref "R1") (pin "1") (pinfunction "1_1") (pintype "passive"))
      (node (ref "U1") (pin "G2") (pinfunction "ODT_CA_A_G2") (pintype "passive"))
    )
    (net (code "64") (name "Net-(U1A-ODT_CA_B)") (class "Default")
      (node (ref "R4") (pin "2") (pinfunction "2_2") (pintype "passive"))
      (node (ref "U1") (pin "T2") (pinfunction "ODT_CA_B_T2") (pintype "passive"))
    )
    (net (code "65") (name "Net-(U1A-ZQ0)") (class "Default")
      (node (ref "R2") (pin "2") (pinfunction "2_2") (pintype "passive"))
      (node (ref "U1") (pin "A5") (pinfunction "ZQ0_A5") (pintype "passive"))
    )
    (net (code "66") (name "Net-(U1A-ZQ1)") (class "Default")
      (node (ref "R3") (pin "2") (pinfunction "2_2") (pintype "passive"))
      (node (ref "U1") (pin "A8") (pinfunction "ZQ1_A8") (pintype "passive"))
    )
    (net (code "67") (name "VCC1V8_LPDDR4_A") (class "Default")
      (node (ref "C19") (pin "2") (pinfunction "2_2") (pintype "passive"))
      (node (ref "C20") (pin "2") (pinfunction "2_2") (pintype "passive"))
      (node (ref "C21") (pin "2") (pinfunction "2_2") (pintype "passive"))
      (node (ref "C22") (pin "2") (pinfunction "2_2") (pintype "passive"))
      (node (ref "C23") (pin "2") (pinfunction "2_2") (pintype "passive"))
      (node (ref "C24") (pin "2") (pinfunction "2_2") (pintype "passive"))
      (node (ref "C25") (pin "2") (pinfunction "2_2") (pintype "passive"))
      (node (ref "C26") (pin "2") (pinfunction "2_2") (pintype "passive"))
      (node (ref "C27") (pin "2") (pinfunction "2_2") (pintype "passive"))
      (node (ref "FB1") (pin "1") (pinfunction "1_1") (pintype "passive"))
      (node (ref "U1") (pin "F1") (pinfunction "VDD1_F1") (pintype "passive"))
      (node (ref "U1") (pin "F12") (pinfunction "VDD1_F12") (pintype "passive"))
      (node (ref "U1") (pin "G4") (pinfunction "VDD1_G4") (pintype "passive"))
      (node (ref "U1") (pin "G9") (pinfunction "VDD1_G9") (pintype "passive"))
      (node (ref "U1") (pin "T4") (pinfunction "VDD1_T4") (pintype "passive"))
      (node (ref "U1") (pin "T9") (pinfunction "VDD1_T9") (pintype "passive"))
      (node (ref "U1") (pin "U1") (pinfunction "VDD1_U1") (pintype "passive"))
      (node (ref "U1") (pin "U12") (pinfunction "VDD1_U12") (pintype "passive"))
    )
    (net (code "68") (name "VCC_DDR") (class "Default")
      (node (ref "C1") (pin "2") (pinfunction "2_2") (pintype "passive"))
      (node (ref "C10") (pin "2") (pinfunction "2_2") (pintype "passive"))
      (node (ref "C11") (pin "2") (pinfunction "2_2") (pintype "passive"))
      (node (ref "C12") (pin "2") (pinfunction "2_2") (pintype "passive"))
      (node (ref "C13") (pin "2") (pinfunction "2_2") (pintype "passive"))
      (node (ref "C14") (pin "2") (pinfunction "2_2") (pintype "passive"))
      (node (ref "C15") (pin "2") (pinfunction "2_2") (pintype "passive"))
      (node (ref "C16") (pin "2") (pinfunction "2_2") (pintype "passive"))
      (node (ref "C17") (pin "2") (pinfunction "2_2") (pintype "passive"))
      (node (ref "C18") (pin "2") (pinfunction "2_2") (pintype "passive"))
      (node (ref "C2") (pin "2") (pinfunction "2_2") (pintype "passive"))
      (node (ref "C3") (pin "2") (pinfunction "2_2") (pintype "passive"))
      (node (ref "C4") (pin "2") (pinfunction "2_2") (pintype "passive"))
      (node (ref "C5") (pin "2") (pinfunction "2_2") (pintype "passive"))
      (node (ref "C6") (pin "2") (pinfunction "2_2") (pintype "passive"))
      (node (ref "C7") (pin "2") (pinfunction "2_2") (pintype "passive"))
      (node (ref "C8") (pin "2") (pinfunction "2_2") (pintype "passive"))
      (node (ref "C9") (pin "2") (pinfunction "2_2") (pintype "passive"))
      (node (ref "FB1") (pin "2") (pinfunction "2_2") (pintype "passive"))
      (node (ref "U1") (pin "A4") (pinfunction "VDD2_A4") (pintype "passive"))
      (node (ref "U1") (pin "A9") (pinfunction "VDD2_A9") (pintype "passive"))
      (node (ref "U1") (pin "AB4") (pinfunction "VDD2_AB4") (pintype "passive"))
      (node (ref "U1") (pin "AB9") (pinfunction "VDD2_AB9") (pintype "passive"))
      (node (ref "U1") (pin "F5") (pinfunction "VDD2_F5") (pintype "passive"))
      (node (ref "U1") (pin "F8") (pinfunction "VDD2_F8") (pintype "passive"))
      (node (ref "U1") (pin "H1") (pinfunction "VDD2_H1") (pintype "passive"))
      (node (ref "U1") (pin "H12") (pinfunction "VDD2_H12") (pintype "passive"))
      (node (ref "U1") (pin "H5") (pinfunction "VDD2_H5") (pintype "passive"))
      (node (ref "U1") (pin "H8") (pinfunction "VDD2_H8") (pintype "passive"))
      (node (ref "U1") (pin "K1") (pinfunction "VDD2_K1") (pintype "passive"))
      (node (ref "U1") (pin "K10") (pinfunction "VDD2_K10") (pintype "passive"))
      (node (ref "U1") (pin "K12") (pinfunction "VDD2_K12") (pintype "passive"))
      (node (ref "U1") (pin "K3") (pinfunction "VDD2_K3") (pintype "passive"))
      (node (ref "U1") (pin "N1") (pinfunction "VDD2_N1") (pintype "passive"))
      (node (ref "U1") (pin "N10") (pinfunction "VDD2_N10") (pintype "passive"))
      (node (ref "U1") (pin "N12") (pinfunction "VDD2_N12") (pintype "passive"))
      (node (ref "U1") (pin "N3") (pinfunction "VDD2_N3") (pintype "passive"))
      (node (ref "U1") (pin "R1") (pinfunction "VDD2_R1") (pintype "passive"))
      (node (ref "U1") (pin "R12") (pinfunction "VDD2_R12") (pintype "passive"))
      (node (ref "U1") (pin "R5") (pinfunction "VDD2_R5") (pintype "passive"))
      (node (ref "U1") (pin "R8") (pinfunction "VDD2_R8") (pintype "passive"))
      (node (ref "U1") (pin "U5") (pinfunction "VDD2_U5") (pintype "passive"))
      (node (ref "U1") (pin "U8") (pinfunction "VDD2_U8") (pintype "passive"))
    )
    (net (code "69") (name "VCC_DDRC") (class "Default")
      (node (ref "C28") (pin "2") (pinfunction "2_2") (pintype "passive"))
      (node (ref "C29") (pin "2") (pinfunction "2_2") (pintype "passive"))
      (node (ref "C30") (pin "2") (pinfunction "2_2") (pintype "passive"))
      (node (ref "C31") (pin "2") (pinfunction "2_2") (pintype "passive"))
      (node (ref "C32") (pin "2") (pinfunction "2_2") (pintype "passive"))
      (node (ref "C33") (pin "2") (pinfunction "2_2") (pintype "passive"))
      (node (ref "C34") (pin "2") (pinfunction "2_2") (pintype "passive"))
      (node (ref "C35") (pin "2") (pinfunction "2_2") (pintype "passive"))
      (node (ref "C36") (pin "2") (pinfunction "2_2") (pintype "passive"))
      (node (ref "C37") (pin "2") (pinfunction "2_2") (pintype "passive"))
      (node (ref "C38") (pin "2") (pinfunction "2_2") (pintype "passive"))
      (node (ref "C39") (pin "2") (pinfunction "2_2") (pintype "passive"))
      (node (ref "C40") (pin "2") (pinfunction "2_2") (pintype "passive"))
      (node (ref "C41") (pin "2") (pinfunction "2_2") (pintype "passive"))
      (node (ref "C42") (pin "2") (pinfunction "2_2") (pintype "passive"))
      (node (ref "C43") (pin "2") (pinfunction "2_2") (pintype "passive"))
      (node (ref "C44") (pin "2") (pinfunction "2_2") (pintype "passive"))
      (node (ref "C45") (pin "2") (pinfunction "2_2") (pintype "passive"))
      (node (ref "R1") (pin "2") (pinfunction "2_2") (pintype "passive"))
      (node (ref "R2") (pin "1") (pinfunction "1_1") (pintype "passive"))
      (node (ref "R3") (pin "1") (pinfunction "1_1") (pintype "passive"))
      (node (ref "U1") (pin "AA10") (pinfunction "VDDQ_AA10") (pintype "passive"))
      (node (ref "U1") (pin "AA3") (pinfunction "VDDQ_AA3") (pintype "passive"))
      (node (ref "U1") (pin "AA5") (pinfunction "VDDQ_AA5") (pintype "passive"))
      (node (ref "U1") (pin "AA8") (pinfunction "VDDQ_AA8") (pintype "passive"))
      (node (ref "U1") (pin "B10") (pinfunction "VDDQ_B10") (pintype "passive"))
      (node (ref "U1") (pin "B3") (pinfunction "VDDQ_B3") (pintype "passive"))
      (node (ref "U1") (pin "B5") (pinfunction "VDDQ_B5") (pintype "passive"))
      (node (ref "U1") (pin "B8") (pinfunction "VDDQ_B8") (pintype "passive"))
      (node (ref "U1") (pin "D1") (pinfunction "VDDQ_D1") (pintype "passive"))
      (node (ref "U1") (pin "D12") (pinfunction "VDDQ_D12") (pintype "passive"))
      (node (ref "U1") (pin "D5") (pinfunction "VDDQ_D5") (pintype "passive"))
      (node (ref "U1") (pin "D8") (pinfunction "VDDQ_D8") (pintype "passive"))
      (node (ref "U1") (pin "F10") (pinfunction "VDDQ_F10") (pintype "passive"))
      (node (ref "U1") (pin "F3") (pinfunction "VDDQ_F3") (pintype "passive"))
      (node (ref "U1") (pin "U10") (pinfunction "VDDQ_U10") (pintype "passive"))
      (node (ref "U1") (pin "U3") (pinfunction "VDDQ_U3") (pintype "passive"))
      (node (ref "U1") (pin "W1") (pinfunction "VDDQ_W1") (pintype "passive"))
      (node (ref "U1") (pin "W12") (pinfunction "VDDQ_W12") (pintype "passive"))
      (node (ref "U1") (pin "W5") (pinfunction "VDDQ_W5") (pintype "passive"))
      (node (ref "U1") (pin "W8") (pinfunction "VDDQ_W8") (pintype "passive"))
    )
    (net (code "70") (name "unconnected-(U1B-DNU1-PadA1)") (class "Default")
      (node (ref "U1") (pin "A1") (pinfunction "DNU1_A1") (pintype "passive+no_connect"))
    )
    (net (code "71") (name "unconnected-(U1B-DNU2-PadA2)") (class "Default")
      (node (ref "U1") (pin "A2") (pinfunction "DNU2_A2") (pintype "passive+no_connect"))
    )
    (net (code "72") (name "unconnected-(U1B-DNU3-PadA11)") (class "Default")
      (node (ref "U1") (pin "A11") (pinfunction "DNU3_A11") (pintype "passive+no_connect"))
    )
    (net (code "73") (name "unconnected-(U1B-DNU4-PadA12)") (class "Default")
      (node (ref "U1") (pin "A12") (pinfunction "DNU4_A12") (pintype "passive+no_connect"))
    )
    (net (code "74") (name "unconnected-(U1B-DNU5-PadB1)") (class "Default")
      (node (ref "U1") (pin "B1") (pinfunction "DNU5_B1") (pintype "passive+no_connect"))
    )
    (net (code "75") (name "unconnected-(U1B-DNU6-PadB12)") (class "Default")
      (node (ref "U1") (pin "B12") (pinfunction "DNU6_B12") (pintype "passive+no_connect"))
    )
    (net (code "76") (name "unconnected-(U1B-DNU7-PadAA1)") (class "Default")
      (node (ref "U1") (pin "AA1") (pinfunction "DNU7_AA1") (pintype "passive+no_connect"))
    )
    (net (code "77") (name "unconnected-(U1B-DNU8-PadAA12)") (class "Default")
      (node (ref "U1") (pin "AA12") (pinfunction "DNU8_AA12") (pintype "passive+no_connect"))
    )
    (net (code "78") (name "unconnected-(U1B-DNU9-PadAB1)") (class "Default")
      (node (ref "U1") (pin "AB1") (pinfunction "DNU9_AB1") (pintype "passive+no_connect"))
    )
    (net (code "79") (name "unconnected-(U1B-DNU10-PadAB2)") (class "Default")
      (node (ref "U1") (pin "AB2") (pinfunction "DNU10_AB2") (pintype "passive+no_connect"))
    )
    (net (code "80") (name "unconnected-(U1B-DNU11-PadAB11)") (class "Default")
      (node (ref "U1") (pin "AB11") (pinfunction "DNU11_AB11") (pintype "passive+no_connect"))
    )
    (net (code "81") (name "unconnected-(U1B-DNU12-PadAB12)") (class "Default")
      (node (ref "U1") (pin "AB12") (pinfunction "DNU12_AB12") (pintype "passive+no_connect"))
    )
    (net (code "82") (name "unconnected-(U1B-DNU13-PadK8)") (class "Default")
      (node (ref "U1") (pin "K8") (pinfunction "DNU13_K8") (pintype "passive+no_connect"))
    )
    (net (code "83") (name "unconnected-(U1B-DNU14-PadN5)") (class "Default")
      (node (ref "U1") (pin "N5") (pinfunction "DNU14_N5") (pintype "passive+no_connect"))
    )
    (net (code "84") (name "unconnected-(U1B-DNU15-PadK5)") (class "Default")
      (node (ref "U1") (pin "K5") (pinfunction "DNU15_K5") (pintype "passive+no_connect"))
    )
    (net (code "85") (name "unconnected-(U1B-DNU16-PadG11)") (class "Default")
      (node (ref "U1") (pin "G11") (pinfunction "DNU16_G11") (pintype "passive+no_connect"))
    )
    (net (code "86") (name "unconnected-(U1B-DNU17-PadN8)") (class "Default")
      (node (ref "U1") (pin "N8") (pinfunction "DNU17_N8") (pintype "passive+no_connect"))
    )
  )
)
